# program_v1_2.net
KiCad netlist of a schematic drawn in EAGLE
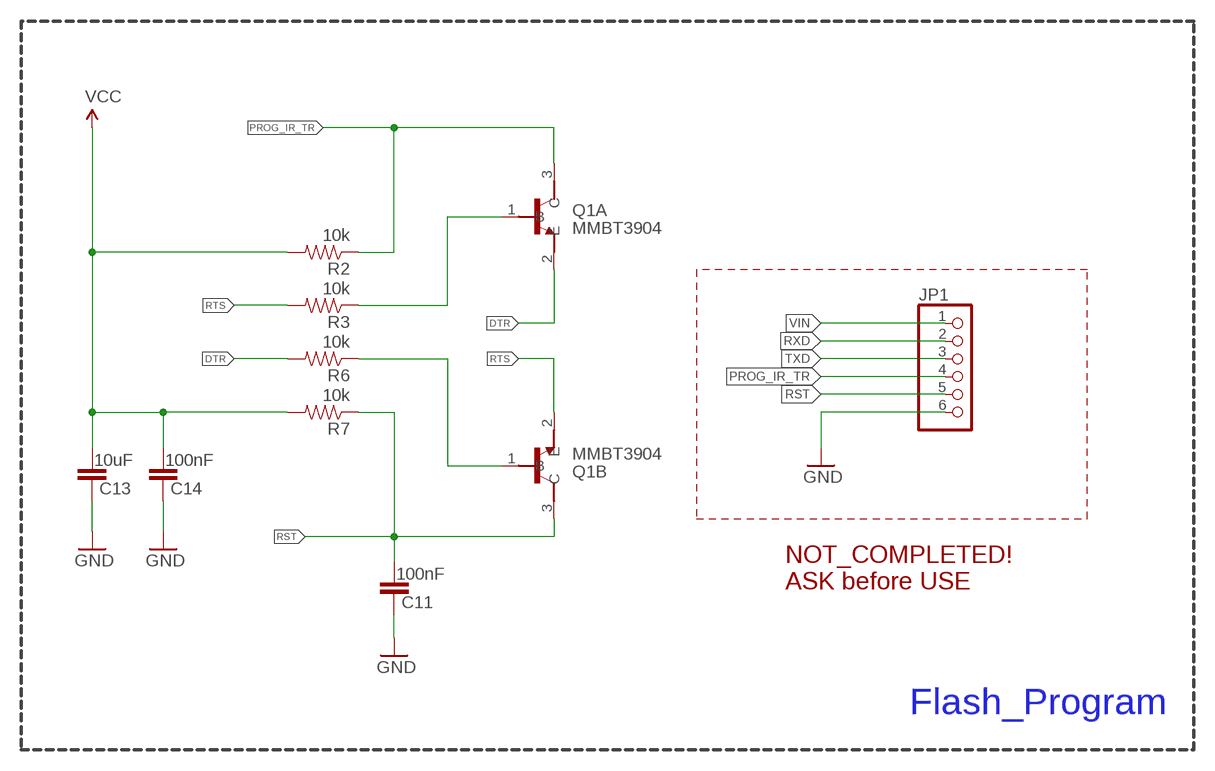
[diagram p0: schematic, sheet 1]

(export (version "E")
  (design (tool "Eeschema 10.0.6"))
  (components
    (comp (ref "C11")
      (value "100nF")
      (footprint "eagle-import:C0805")
      (libsource (lib "eagle-import") (part "C-EUC0805"))
    )
    (comp (ref "C13")
      (value "10uF")
      (footprint "eagle-import:C0805")
      (libsource (lib "eagle-import") (part "C-EUC0805"))
    )
    (comp (ref "C14")
      (value "100nF")
      (footprint "eagle-import:C0805")
      (libsource (lib "eagle-import") (part "C-EUC0805"))
    )
    (comp (ref "JP1")
      (value "PINHD-1X6")
      (footprint "eagle-import:1X06")
      (libsource (lib "eagle-import") (part "PINHD-1X6"))
    )
    (comp (ref "Q1A")
      (value "MMBT3904")
      (footprint "eagle-import:SOT95P240X120-3N")
      (fields (field (name "MF") "STMicroelectronics"))
      (libsource (lib "eagle-import") (part "MMBT3904"))
    )
    (comp (ref "Q1B")
      (value "MMBT3904")
      (footprint "eagle-import:SOT95P240X120-3N")
      (fields (field (name "MF") "STMicroelectronics"))
      (libsource (lib "eagle-import") (part "MMBT3904"))
    )
    (comp (ref "R2")
      (value "10k")
      (footprint "eagle-import:SPARKFUN_0805")
      (libsource (lib "eagle-import") (part "SPARKFUN_RESISTOR0805-RES"))
    )
    (comp (ref "R3")
      (value "10k")
      (footprint "eagle-import:SPARKFUN_0805")
      (libsource (lib "eagle-import") (part "SPARKFUN_RESISTOR0805-RES"))
    )
    (comp (ref "R6")
      (value "10k")
      (footprint "eagle-import:SPARKFUN_0805")
      (libsource (lib "eagle-import") (part "SPARKFUN_RESISTOR0805-RES"))
    )
    (comp (ref "R7")
      (value "10k")
      (footprint "eagle-import:SPARKFUN_0805")
      (libsource (lib "eagle-import") (part "SPARKFUN_RESISTOR0805-RES"))
    )
  )
  (nets
    (net (code "1") (name "DTR") (class "Default")
      (node (ref "Q1A") (pin "2") (pinfunction "E_2") (pintype "passive"))
      (node (ref "R6") (pin "2") (pinfunction "2_2") (pintype "passive"))
    )
    (net (code "2") (name "GND") (class "Default")
      (node (ref "C11") (pin "1") (pinfunction "1_1") (pintype "passive"))
      (node (ref "C13") (pin "1") (pinfunction "1_1") (pintype "passive"))
      (node (ref "C14") (pin "1") (pinfunction "1_1") (pintype "passive"))
      (node (ref "JP1") (pin "6") (pinfunction "6_6") (pintype "passive"))
    )
    (net (code "3") (name "Net-(Q1A-B)") (class "Default")
      (node (ref "Q1A") (pin "1") (pinfunction "B_1") (pintype "passive"))
      (node (ref "R3") (pin "1") (pinfunction "1_1") (pintype "passive"))
    )
    (net (code "4") (name "Net-(Q1B-B)") (class "Default")
      (node (ref "Q1B") (pin "1") (pinfunction "B_1") (pintype "passive"))
      (node (ref "R6") (pin "1") (pinfunction "1_1") (pintype "passive"))
    )
    (net (code "5") (name "PROG_IR_TR") (class "Default")
      (node (ref "JP1") (pin "4") (pinfunction "4_4") (pintype "passive"))
      (node (ref "Q1A") (pin "3") (pinfunction "C_3") (pintype "passive"))
      (node (ref "R2") (pin "1") (pinfunction "1_1") (pintype "passive"))
    )
    (net (code "6") (name "RST") (class "Default")
      (node (ref "C11") (pin "2") (pinfunction "2_2") (pintype "passive"))
      (node (ref "JP1") (pin "5") (pinfunction "5_5") (pintype "passive"))
      (node (ref "Q1B") (pin "3") (pinfunction "C_3") (pintype "passive"))
      (node (ref "R7") (pin "1") (pinfunction "1_1") (pintype "passive"))
    )
    (net (code "7") (name "RTS") (class "Default")
      (node (ref "Q1B") (pin "2") (pinfunction "E_2") (pintype "passive"))
      (node (ref "R3") (pin "2") (pinfunction "2_2") (pintype "passive"))
    )
    (net (code "8") (name "RXD") (class "Default")
      (node (ref "JP1") (pin "2") (pinfunction "2_2") (pintype "passive"))
    )
    (net (code "9") (name "TXD") (class "Default")
      (node (ref "JP1") (pin "3") (pinfunction "3_3") (pintype "passive"))
    )
    (net (code "10") (name "VCC") (class "Default")
      (node (ref "C13") (pin "2") (pinfunction "2_2") (pintype "passive"))
      (node (ref "C14") (pin "2") (pinfunction "2_2") (pintype "passive"))
      (node (ref "R2") (pin "2") (pinfunction "2_2") (pintype "passive"))
      (node (ref "R7") (pin "2") (pinfunction "2_2") (pintype "passive"))
    )
    (net (code "11") (name "VIN") (class "Default")
      (node (ref "JP1") (pin "1") (pinfunction "1_1") (pintype "passive"))
    )
  )
)
